# Solenoids.net
KiCad netlist of a schematic drawn in EAGLE
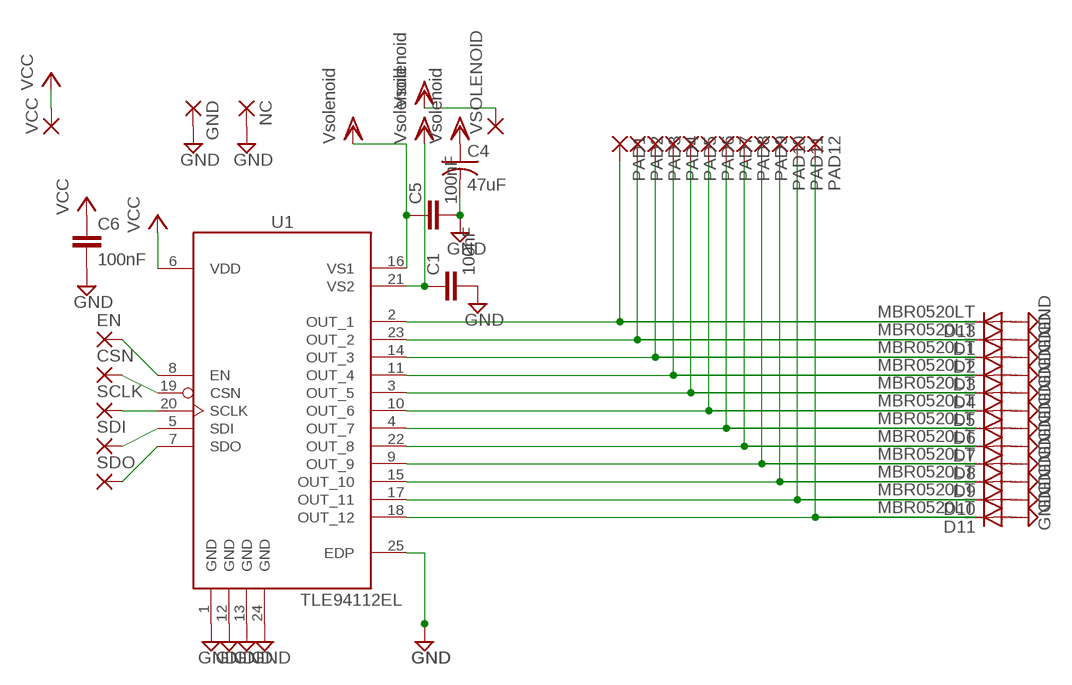
[diagram p0: schematic, sheet 1]

(export (version "E")
  (design (tool "Eeschema 10.0.6"))
  (components
    (comp (ref "C1")
      (value "100nF")
      (footprint "eagle-import:C0402K")
      (libsource (lib "eagle-import") (part "C-EUC0402K"))
    )
    (comp (ref "C4")
      (value "47uF")
      (footprint "eagle-import:C050-045X075")
      (libsource (lib "eagle-import") (part "C-US050-045X075"))
    )
    (comp (ref "C5")
      (value "100nF")
      (footprint "eagle-import:C0402K")
      (libsource (lib "eagle-import") (part "C-EUC0402K"))
    )
    (comp (ref "C6")
      (value "100nF")
      (footprint "eagle-import:C0402K")
      (libsource (lib "eagle-import") (part "C-EUC0402K"))
    )
    (comp (ref "CSN")
      (value "1,6/0,8")
      (footprint "eagle-import:1,6_0,8")
      (libsource (lib "eagle-import") (part "1,6/0,8"))
    )
    (comp (ref "D1")
      (value "MBR0520LT")
      (footprint "eagle-import:SOD123")
      (libsource (lib "eagle-import") (part "MBR0520LT"))
    )
    (comp (ref "D2")
      (value "MBR0520LT")
      (footprint "eagle-import:SOD123")
      (libsource (lib "eagle-import") (part "MBR0520LT"))
    )
    (comp (ref "D3")
      (value "MBR0520LT")
      (footprint "eagle-import:SOD123")
      (libsource (lib "eagle-import") (part "MBR0520LT"))
    )
    (comp (ref "D4")
      (value "MBR0520LT")
      (footprint "eagle-import:SOD123")
      (libsource (lib "eagle-import") (part "MBR0520LT"))
    )
    (comp (ref "D5")
      (value "MBR0520LT")
      (footprint "eagle-import:SOD123")
      (libsource (lib "eagle-import") (part "MBR0520LT"))
    )
    (comp (ref "D6")
      (value "MBR0520LT")
      (footprint "eagle-import:SOD123")
      (libsource (lib "eagle-import") (part "MBR0520LT"))
    )
    (comp (ref "D7")
      (value "MBR0520LT")
      (footprint "eagle-import:SOD123")
      (libsource (lib "eagle-import") (part "MBR0520LT"))
    )
    (comp (ref "D8")
      (value "MBR0520LT")
      (footprint "eagle-import:SOD123")
      (libsource (lib "eagle-import") (part "MBR0520LT"))
    )
    (comp (ref "D9")
      (value "MBR0520LT")
      (footprint "eagle-import:SOD123")
      (libsource (lib "eagle-import") (part "MBR0520LT"))
    )
    (comp (ref "D10")
      (value "MBR0520LT")
      (footprint "eagle-import:SOD123")
      (libsource (lib "eagle-import") (part "MBR0520LT"))
    )
    (comp (ref "D11")
      (value "MBR0520LT")
      (footprint "eagle-import:SOD123")
      (libsource (lib "eagle-import") (part "MBR0520LT"))
    )
    (comp (ref "D13")
      (value "MBR0520LT")
      (footprint "eagle-import:SOD123")
      (libsource (lib "eagle-import") (part "MBR0520LT"))
    )
    (comp (ref "EN")
      (value "1,6/0,8")
      (footprint "eagle-import:1,6_0,8")
      (libsource (lib "eagle-import") (part "1,6/0,8"))
    )
    (comp (ref "GND")
      (value "1,6/0,8")
      (footprint "eagle-import:1,6_0,8")
      (libsource (lib "eagle-import") (part "1,6/0,8"))
    )
    (comp (ref "NC")
      (value "1,6/0,8")
      (footprint "eagle-import:1,6_0,8")
      (libsource (lib "eagle-import") (part "1,6/0,8"))
    )
    (comp (ref "PAD1")
      (value "1,6/0,8")
      (footprint "eagle-import:1,6_0,8")
      (libsource (lib "eagle-import") (part "1,6/0,8"))
    )
    (comp (ref "PAD2")
      (value "1,6/0,8")
      (footprint "eagle-import:1,6_0,8")
      (libsource (lib "eagle-import") (part "1,6/0,8"))
    )
    (comp (ref "PAD3")
      (value "1,6/0,8")
      (footprint "eagle-import:1,6_0,8")
      (libsource (lib "eagle-import") (part "1,6/0,8"))
    )
    (comp (ref "PAD4")
      (value "1,6/0,8")
      (footprint "eagle-import:1,6_0,8")
      (libsource (lib "eagle-import") (part "1,6/0,8"))
    )
    (comp (ref "PAD5")
      (value "1,6/0,8")
      (footprint "eagle-import:1,6_0,8")
      (libsource (lib "eagle-import") (part "1,6/0,8"))
    )
    (comp (ref "PAD6")
      (value "1,6/0,8")
      (footprint "eagle-import:1,6_0,8")
      (libsource (lib "eagle-import") (part "1,6/0,8"))
    )
    (comp (ref "PAD7")
      (value "1,6/0,8")
      (footprint "eagle-import:1,6_0,8")
      (libsource (lib "eagle-import") (part "1,6/0,8"))
    )
    (comp (ref "PAD8")
      (value "1,6/0,8")
      (footprint "eagle-import:1,6_0,8")
      (libsource (lib "eagle-import") (part "1,6/0,8"))
    )
    (comp (ref "PAD9")
      (value "1,6/0,8")
      (footprint "eagle-import:1,6_0,8")
      (libsource (lib "eagle-import") (part "1,6/0,8"))
    )
    (comp (ref "PAD10")
      (value "1,6/0,8")
      (footprint "eagle-import:1,6_0,8")
      (libsource (lib "eagle-import") (part "1,6/0,8"))
    )
    (comp (ref "PAD11")
      (value "1,6/0,8")
      (footprint "eagle-import:1,6_0,8")
      (libsource (lib "eagle-import") (part "1,6/0,8"))
    )
    (comp (ref "PAD12")
      (value "1,6/0,8")
      (footprint "eagle-import:1,6_0,8")
      (libsource (lib "eagle-import") (part "1,6/0,8"))
    )
    (comp (ref "SCLK")
      (value "1,6/0,8")
      (footprint "eagle-import:1,6_0,8")
      (libsource (lib "eagle-import") (part "1,6/0,8"))
    )
    (comp (ref "SDI")
      (value "1,6/0,8")
      (footprint "eagle-import:1,6_0,8")
      (libsource (lib "eagle-import") (part "1,6/0,8"))
    )
    (comp (ref "SDO")
      (value "1,6/0,8")
      (footprint "eagle-import:1,6_0,8")
      (libsource (lib "eagle-import") (part "1,6/0,8"))
    )
    (comp (ref "U1")
      (value "TLE94112EL")
      (footprint "eagle-import:SOP65P600X170-25N")
      (libsource (lib "eagle-import") (part "TLE94112EL"))
    )
    (comp (ref "VCC")
      (value "1,6/0,8")
      (footprint "eagle-import:1,6_0,8")
      (libsource (lib "eagle-import") (part "1,6/0,8"))
    )
    (comp (ref "VSOLENOID")
      (value "1,6/0,8")
      (footprint "eagle-import:1,6_0,8")
      (libsource (lib "eagle-import") (part "1,6/0,8"))
    )
  )
  (nets
    (net (code "1") (name "GND") (class "Default")
      (node (ref "C1") (pin "2") (pinfunction "2_2") (pintype "passive"))
      (node (ref "C4") (pin "2") (pinfunction "2_2") (pintype "passive"))
      (node (ref "C5") (pin "2") (pinfunction "2_2") (pintype "passive"))
      (node (ref "C6") (pin "2") (pinfunction "2_2") (pintype "passive"))
      (node (ref "D1") (pin "A") (pinfunction "A_A") (pintype "passive"))
      (node (ref "D10") (pin "A") (pinfunction "A_A") (pintype "passive"))
      (node (ref "D11") (pin "A") (pinfunction "A_A") (pintype "passive"))
      (node (ref "D13") (pin "A") (pinfunction "A_A") (pintype "passive"))
      (node (ref "D2") (pin "A") (pinfunction "A_A") (pintype "passive"))
      (node (ref "D3") (pin "A") (pinfunction "A_A") (pintype "passive"))
      (node (ref "D4") (pin "A") (pinfunction "A_A") (pintype "passive"))
      (node (ref "D5") (pin "A") (pinfunction "A_A") (pintype "passive"))
      (node (ref "D6") (pin "A") (pinfunction "A_A") (pintype "passive"))
      (node (ref "D7") (pin "A") (pinfunction "A_A") (pintype "passive"))
      (node (ref "D8") (pin "A") (pinfunction "A_A") (pintype "passive"))
      (node (ref "D9") (pin "A") (pinfunction "A_A") (pintype "passive"))
      (node (ref "GND") (pin "1") (pinfunction "P_1") (pintype "passive"))
      (node (ref "NC") (pin "1") (pinfunction "P_1") (pintype "passive"))
      (node (ref "U1") (pin "1") (pinfunction "GND_1") (pintype "power_in"))
      (node (ref "U1") (pin "12") (pinfunction "GND_12") (pintype "power_in"))
      (node (ref "U1") (pin "13") (pinfunction "GND_13") (pintype "power_in"))
      (node (ref "U1") (pin "24") (pinfunction "GND_24") (pintype "power_in"))
      (node (ref "U1") (pin "25") (pinfunction "EDP_25") (pintype "power_in"))
    )
    (net (code "2") (name "Net-(CSN-P)") (class "Default")
      (node (ref "CSN") (pin "1") (pinfunction "P_1") (pintype "passive"))
      (node (ref "U1") (pin "19") (pinfunction "CSN_19") (pintype "input"))
    )
    (net (code "3") (name "Net-(EN-P)") (class "Default")
      (node (ref "EN") (pin "1") (pinfunction "P_1") (pintype "passive"))
      (node (ref "U1") (pin "8") (pinfunction "EN_8") (pintype "input"))
    )
    (net (code "4") (name "Net-(PAD1-P)") (class "Default")
      (node (ref "D13") (pin "C") (pinfunction "C_C") (pintype "passive"))
      (node (ref "PAD1") (pin "1") (pinfunction "P_1") (pintype "passive"))
      (node (ref "U1") (pin "2") (pinfunction "OUT_1_2") (pintype "output"))
    )
    (net (code "5") (name "Net-(PAD2-P)") (class "Default")
      (node (ref "D1") (pin "C") (pinfunction "C_C") (pintype "passive"))
      (node (ref "PAD2") (pin "1") (pinfunction "P_1") (pintype "passive"))
      (node (ref "U1") (pin "23") (pinfunction "OUT_2_23") (pintype "output"))
    )
    (net (code "6") (name "Net-(PAD3-P)") (class "Default")
      (node (ref "D2") (pin "C") (pinfunction "C_C") (pintype "passive"))
      (node (ref "PAD3") (pin "1") (pinfunction "P_1") (pintype "passive"))
      (node (ref "U1") (pin "14") (pinfunction "OUT_3_14") (pintype "output"))
    )
    (net (code "7") (name "Net-(PAD4-P)") (class "Default")
      (node (ref "D3") (pin "C") (pinfunction "C_C") (pintype "passive"))
      (node (ref "PAD4") (pin "1") (pinfunction "P_1") (pintype "passive"))
      (node (ref "U1") (pin "11") (pinfunction "OUT_4_11") (pintype "output"))
    )
    (net (code "8") (name "Net-(PAD5-P)") (class "Default")
      (node (ref "D4") (pin "C") (pinfunction "C_C") (pintype "passive"))
      (node (ref "PAD5") (pin "1") (pinfunction "P_1") (pintype "passive"))
      (node (ref "U1") (pin "3") (pinfunction "OUT_5_3") (pintype "output"))
    )
    (net (code "9") (name "Net-(PAD6-P)") (class "Default")
      (node (ref "D5") (pin "C") (pinfunction "C_C") (pintype "passive"))
      (node (ref "PAD6") (pin "1") (pinfunction "P_1") (pintype "passive"))
      (node (ref "U1") (pin "10") (pinfunction "OUT_6_10") (pintype "output"))
    )
    (net (code "10") (name "Net-(PAD7-P)") (class "Default")
      (node (ref "D6") (pin "C") (pinfunction "C_C") (pintype "passive"))
      (node (ref "PAD7") (pin "1") (pinfunction "P_1") (pintype "passive"))
      (node (ref "U1") (pin "4") (pinfunction "OUT_7_4") (pintype "output"))
    )
    (net (code "11") (name "Net-(PAD8-P)") (class "Default")
      (node (ref "D7") (pin "C") (pinfunction "C_C") (pintype "passive"))
      (node (ref "PAD8") (pin "1") (pinfunction "P_1") (pintype "passive"))
      (node (ref "U1") (pin "22") (pinfunction "OUT_8_22") (pintype "output"))
    )
    (net (code "12") (name "Net-(PAD9-P)") (class "Default")
      (node (ref "D8") (pin "C") (pinfunction "C_C") (pintype "passive"))
      (node (ref "PAD9") (pin "1") (pinfunction "P_1") (pintype "passive"))
      (node (ref "U1") (pin "9") (pinfunction "OUT_9_9") (pintype "output"))
    )
    (net (code "13") (name "Net-(PAD10-P)") (class "Default")
      (node (ref "D9") (pin "C") (pinfunction "C_C") (pintype "passive"))
      (node (ref "PAD10") (pin "1") (pinfunction "P_1") (pintype "passive"))
      (node (ref "U1") (pin "15") (pinfunction "OUT_10_15") (pintype "output"))
    )
    (net (code "14") (name "Net-(PAD11-P)") (class "Default")
      (node (ref "D10") (pin "C") (pinfunction "C_C") (pintype "passive"))
      (node (ref "PAD11") (pin "1") (pinfunction "P_1") (pintype "passive"))
      (node (ref "U1") (pin "17") (pinfunction "OUT_11_17") (pintype "output"))
    )
    (net (code "15") (name "Net-(PAD12-P)") (class "Default")
      (node (ref "D11") (pin "C") (pinfunction "C_C") (pintype "passive"))
      (node (ref "PAD12") (pin "1") (pinfunction "P_1") (pintype "passive"))
      (node (ref "U1") (pin "18") (pinfunction "OUT_12_18") (pintype "output"))
    )
    (net (code "16") (name "Net-(SCLK-P)") (class "Default")
      (node (ref "SCLK") (pin "1") (pinfunction "P_1") (pintype "passive"))
      (node (ref "U1") (pin "20") (pinfunction "SCLK_20") (pintype "input"))
    )
    (net (code "17") (name "Net-(SDI-P)") (class "Default")
      (node (ref "SDI") (pin "1") (pinfunction "P_1") (pintype "passive"))
      (node (ref "U1") (pin "5") (pinfunction "SDI_5") (pintype "input"))
    )
    (net (code "18") (name "Net-(SDO-P)") (class "Default")
      (node (ref "SDO") (pin "1") (pinfunction "P_1") (pintype "passive"))
      (node (ref "U1") (pin "7") (pinfunction "SDO_7") (pintype "output"))
    )
    (net (code "19") (name "VCC") (class "Default")
      (node (ref "C6") (pin "1") (pinfunction "1_1") (pintype "passive"))
      (node (ref "U1") (pin "6") (pinfunction "VDD_6") (pintype "power_in"))
      (node (ref "VCC") (pin "1") (pinfunction "P_1") (pintype "passive"))
    )
    (net (code "20") (name "Vsolenoid") (class "Default")
      (node (ref "C1") (pin "1") (pinfunction "1_1") (pintype "passive"))
      (node (ref "C4") (pin "1") (pinfunction "1_1") (pintype "passive"))
      (node (ref "C5") (pin "1") (pinfunction "1_1") (pintype "passive"))
      (node (ref "U1") (pin "16") (pinfunction "VS1_16") (pintype "power_in"))
      (node (ref "U1") (pin "21") (pinfunction "VS2_21") (pintype "power_in"))
      (node (ref "VSOLENOID") (pin "1") (pinfunction "P_1") (pintype "passive"))
    )
  )
)
